# keychain_rev4.net
KiCad netlist of a schematic drawn in EAGLE
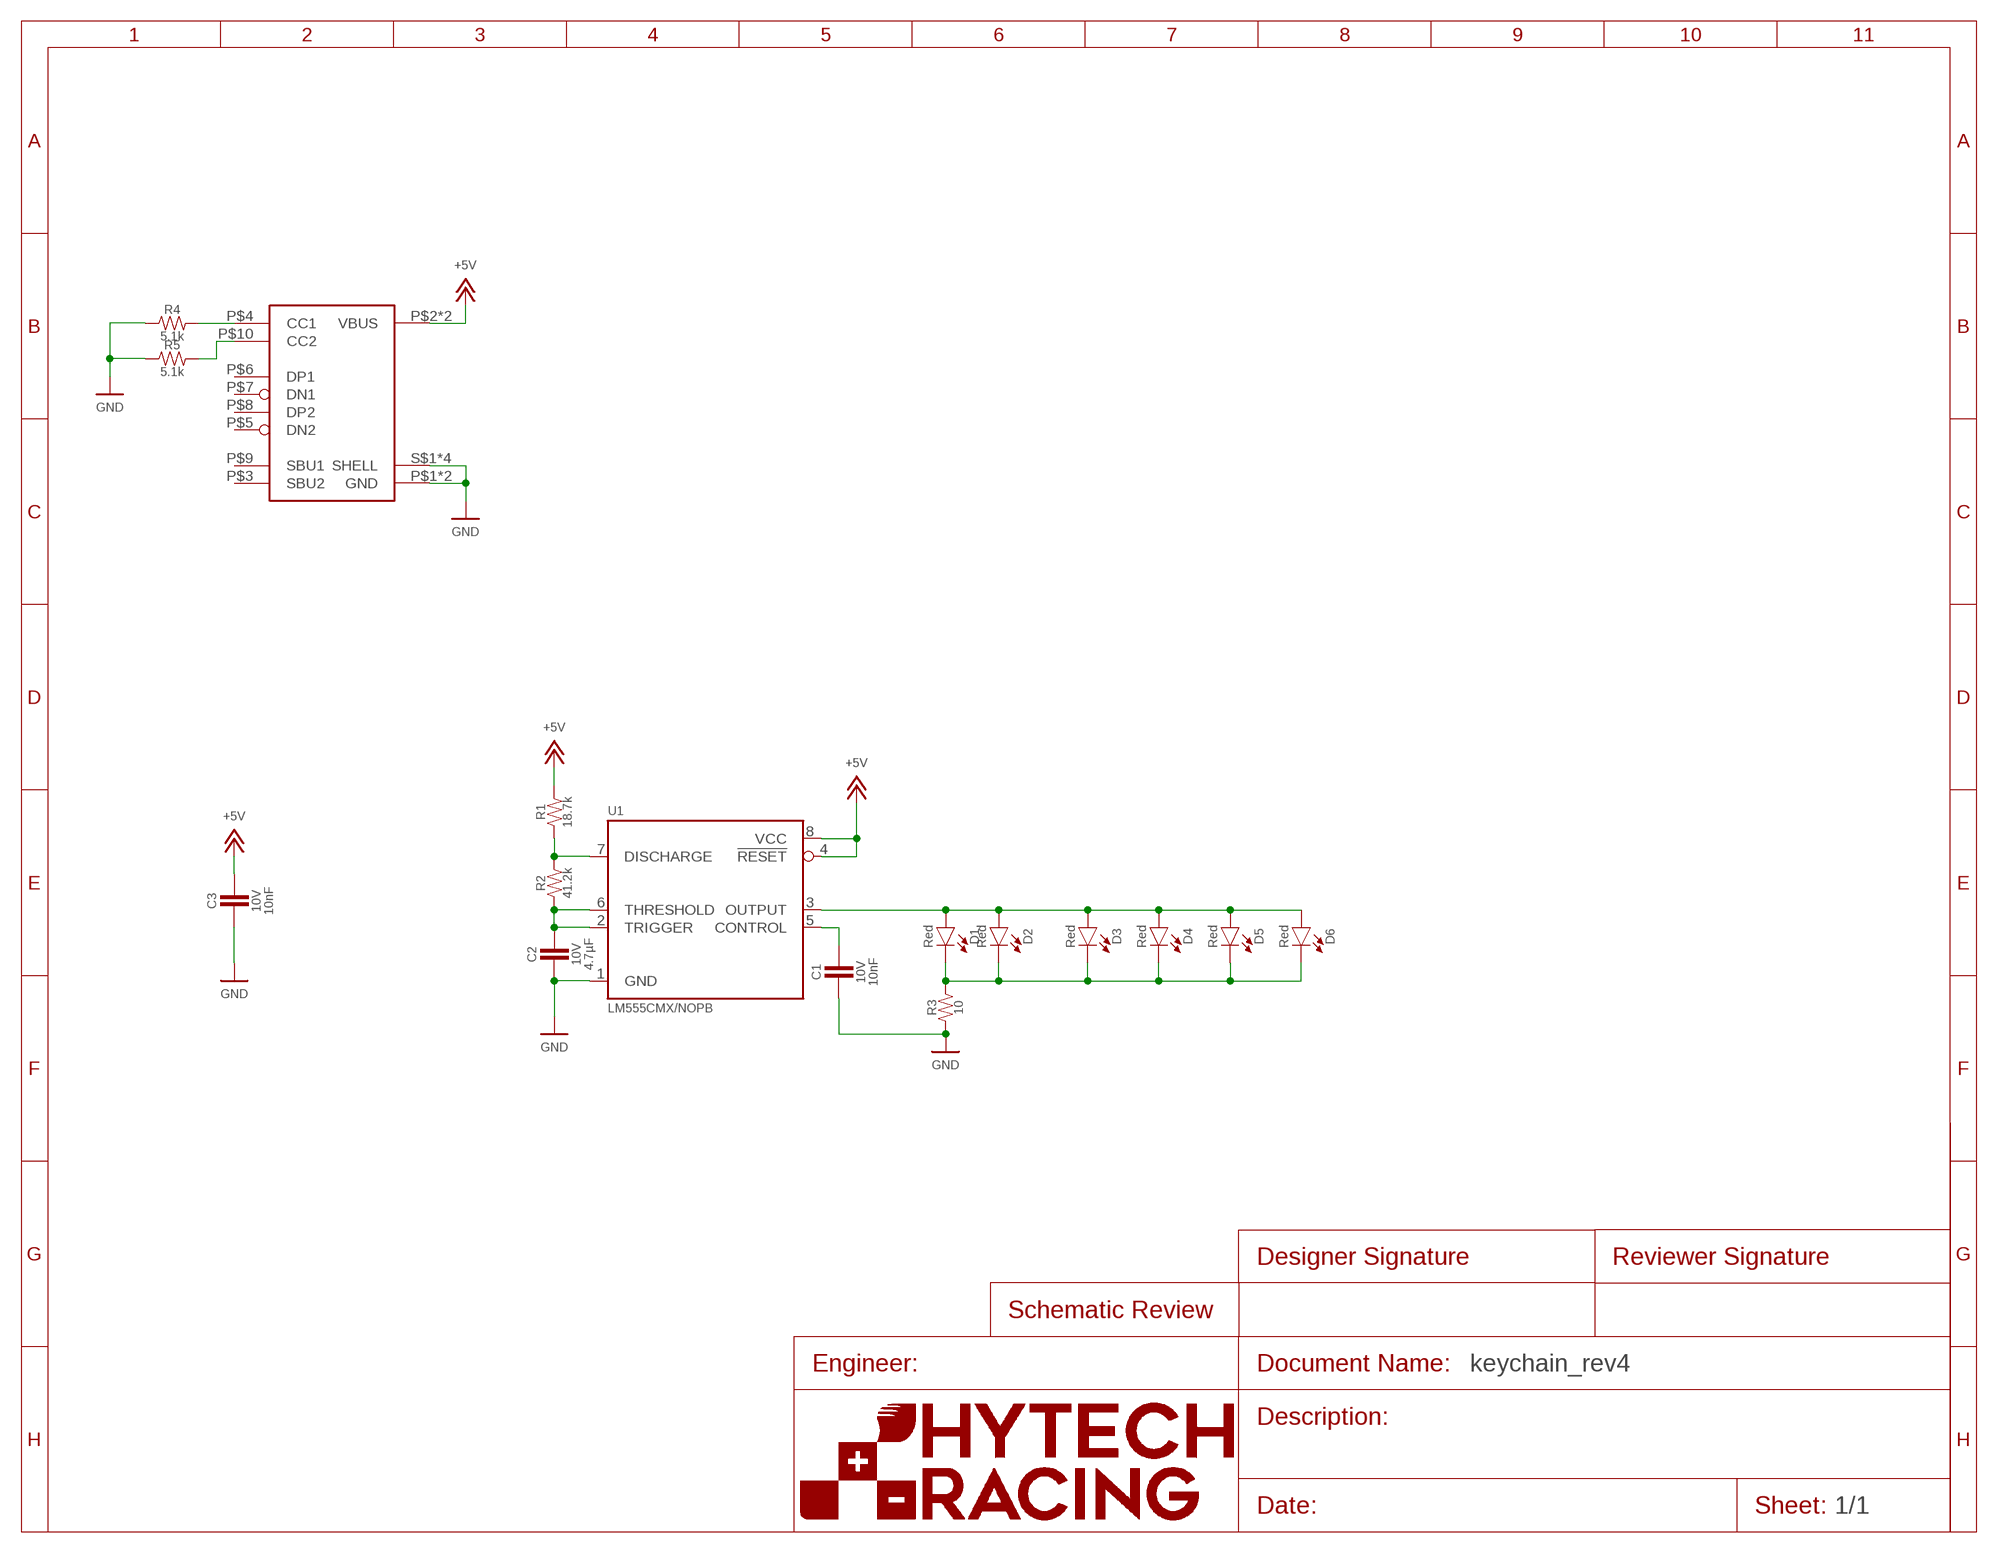
[diagram p0: schematic, sheet 1]

(export (version "E")
  (design (tool "Eeschema 10.0.6"))
  (components
    (comp (ref "C1")
      (value "CAPACITOR_0603_10V_10NF")
      (footprint "eagle-import:0603-CAP")
      (fields
        (field (name "CAPACITANCE") "10nF")
        (field (name "MANUFACTURER") "Yageo")
        (field (name "MPN") "CC0603KRX7R6BB103")
        (field (name "TOLERANCE") "10%")
        (field (name "VOLTAGE") "10V")
      )
      (libsource (lib "eagle-import") (part "CAPACITOR_?_060310V_10NF"))
    )
    (comp (ref "C2")
      (value "CAPACITOR_0603_10V_4.7UF")
      (footprint "eagle-import:0603-CAP")
      (fields
        (field (name "CAPACITANCE") "4.7µF")
        (field (name "MANUFACTURER") "Samsung Electro-Mechanics")
        (field (name "MPN") "CL10A475KP8NNNC")
        (field (name "TOLERANCE") "10%")
        (field (name "VOLTAGE") "10V")
      )
      (libsource (lib "eagle-import") (part "CAPACITOR_?_060310V_4.7UF"))
    )
    (comp (ref "C3")
      (value "CAPACITOR_0603_10V_10NF")
      (footprint "eagle-import:0603-CAP")
      (fields
        (field (name "CAPACITANCE") "10nF")
        (field (name "MANUFACTURER") "Yageo")
        (field (name "MPN") "CC0603KRX7R6BB103")
        (field (name "TOLERANCE") "10%")
        (field (name "VOLTAGE") "10V")
      )
      (libsource (lib "eagle-import") (part "CAPACITOR_?_060310V_10NF"))
    )
    (comp (ref "D1")
      (value "LED_0603_RED")
      (footprint "eagle-import:0603-LED")
      (fields
        (field (name "COLOR") "Red")
        (field (name "MANUFACTURER") "Kingbright")
        (field (name "MPN") "APT1608SECK/J3-PRV")
      )
      (libsource (lib "eagle-import") (part "LED_?_0603RED"))
    )
    (comp (ref "D2")
      (value "LED_0603_RED")
      (footprint "eagle-import:0603-LED")
      (fields
        (field (name "COLOR") "Red")
        (field (name "MANUFACTURER") "Kingbright")
        (field (name "MPN") "APT1608SECK/J3-PRV")
      )
      (libsource (lib "eagle-import") (part "LED_?_0603RED"))
    )
    (comp (ref "D3")
      (value "LED_0603_RED")
      (footprint "eagle-import:0603-LED")
      (fields
        (field (name "COLOR") "Red")
        (field (name "MANUFACTURER") "Kingbright")
        (field (name "MPN") "APT1608SECK/J3-PRV")
      )
      (libsource (lib "eagle-import") (part "LED_?_0603RED"))
    )
    (comp (ref "D4")
      (value "LED_0603_RED")
      (footprint "eagle-import:0603-LED")
      (fields
        (field (name "COLOR") "Red")
        (field (name "MANUFACTURER") "Kingbright")
        (field (name "MPN") "APT1608SECK/J3-PRV")
      )
      (libsource (lib "eagle-import") (part "LED_?_0603RED"))
    )
    (comp (ref "D5")
      (value "LED_0603_RED")
      (footprint "eagle-import:0603-LED")
      (fields
        (field (name "COLOR") "Red")
        (field (name "MANUFACTURER") "Kingbright")
        (field (name "MPN") "APT1608SECK/J3-PRV")
      )
      (libsource (lib "eagle-import") (part "LED_?_0603RED"))
    )
    (comp (ref "D6")
      (value "LED_0603_RED")
      (footprint "eagle-import:0603-LED")
      (fields
        (field (name "COLOR") "Red")
        (field (name "MANUFACTURER") "Kingbright")
        (field (name "MPN") "APT1608SECK/J3-PRV")
      )
      (libsource (lib "eagle-import") (part "LED_?_0603RED"))
    )
    (comp (ref "J1")
      (value "USB4110")
      (footprint "eagle-import:USB4110")
      (fields (field (name "MANUFACTURER") "GCT") (field (name "MPN") "USB4110 "))
      (libsource (lib "eagle-import") (part "USB4110"))
    )
    (comp (ref "R1")
      (value "RESISTOR_0603_18.7K")
      (footprint "eagle-import:0603-RES")
      (fields
        (field (name "MANUFACTURER") "Yageo")
        (field (name "MPN") "RC0603FR-0718K7L")
        (field (name "POWER") "0.1W")
        (field (name "RESISTANCE") "18.7k")
      )
      (libsource (lib "eagle-import") (part "RESISTOR_?_060318.7K"))
    )
    (comp (ref "R2")
      (value "RESISTOR_0603_41.2K")
      (footprint "eagle-import:0603-RES")
      (fields
        (field (name "MANUFACTURER") "Panasonic Electronic Components")
        (field (name "MPN") " ERJ-PB3B4122V")
        (field (name "POWER") "0.2W")
        (field (name "RESISTANCE") "41.2k")
      )
      (libsource (lib "eagle-import") (part "RESISTOR_?_060341.2K"))
    )
    (comp (ref "R3")
      (value "RESISTOR_0603_10")
      (footprint "eagle-import:0603-RES")
      (fields
        (field (name "MANUFACTURER") "Yageo")
        (field (name "MPN") "RC0603FR-0710RL")
        (field (name "POWER") "0.1W")
        (field (name "RESISTANCE") "10")
      )
      (libsource (lib "eagle-import") (part "RESISTOR_?_060310"))
    )
    (comp (ref "R4")
      (value "RESISTOR_0603_5.1K")
      (footprint "eagle-import:0603-RES")
      (fields
        (field (name "MANUFACTURER") "Yageo")
        (field (name "MPN") "RC0603FR-075K1L")
        (field (name "POWER") "0.1W")
        (field (name "RESISTANCE") "5.1k")
      )
      (libsource (lib "eagle-import") (part "RESISTOR_?_06035.1K"))
    )
    (comp (ref "R5")
      (value "RESISTOR_0603_5.1K")
      (footprint "eagle-import:0603-RES")
      (fields
        (field (name "MANUFACTURER") "Yageo")
        (field (name "MPN") "RC0603FR-075K1L")
        (field (name "POWER") "0.1W")
        (field (name "RESISTANCE") "5.1k")
      )
      (libsource (lib "eagle-import") (part "RESISTOR_?_06035.1K"))
    )
    (comp (ref "U1")
      (value "LM555")
      (footprint "eagle-import:SOIC-08(NARROW,0.15_)")
      (fields (field (name "MANUFACTURER") "Texas Instruments") (field (name "MPN") "LM555CMX/NOPB"))
      (libsource (lib "eagle-import") (part "555LM"))
    )
  )
  (nets
    (net (code "1") (name "+5V") (class "Default")
      (node (ref "C3") (pin "1") (pinfunction "1_1") (pintype "passive"))
      (node (ref "J1") (pin "P$11") (pinfunction "VBUS_P$11") (pintype "power_in"))
      (node (ref "J1") (pin "P$2") (pinfunction "VBUS_P$2") (pintype "power_in"))
      (node (ref "R1") (pin "2") (pinfunction "2_2") (pintype "passive"))
      (node (ref "U1") (pin "4") (pinfunction "~{RESET}_4") (pintype "input"))
      (node (ref "U1") (pin "8") (pinfunction "VCC_8") (pintype "power_in"))
    )
    (net (code "2") (name "GND") (class "Default")
      (node (ref "C1") (pin "2") (pinfunction "2_2") (pintype "passive"))
      (node (ref "C2") (pin "2") (pinfunction "2_2") (pintype "passive"))
      (node (ref "C3") (pin "2") (pinfunction "2_2") (pintype "passive"))
      (node (ref "J1") (pin "P$1") (pinfunction "GND_P$1") (pintype "power_in"))
      (node (ref "J1") (pin "P$12") (pinfunction "GND_P$12") (pintype "power_in"))
      (node (ref "J1") (pin "S$1") (pinfunction "SHELL_S$1") (pintype "power_in"))
      (node (ref "J1") (pin "S$2") (pinfunction "SHELL_S$2") (pintype "power_in"))
      (node (ref "J1") (pin "S$3") (pinfunction "SHELL_S$3") (pintype "power_in"))
      (node (ref "J1") (pin "S$4") (pinfunction "SHELL_S$4") (pintype "power_in"))
      (node (ref "R3") (pin "1") (pinfunction "1_1") (pintype "passive"))
      (node (ref "R4") (pin "1") (pinfunction "1_1") (pintype "passive"))
      (node (ref "R5") (pin "1") (pinfunction "1_1") (pintype "passive"))
      (node (ref "U1") (pin "1") (pinfunction "GND_1") (pintype "power_in"))
    )
    (net (code "3") (name "Net-(D1-A)") (class "Default")
      (node (ref "D1") (pin "2") (pinfunction "A_2") (pintype "passive"))
      (node (ref "D2") (pin "2") (pinfunction "A_2") (pintype "passive"))
      (node (ref "D3") (pin "2") (pinfunction "A_2") (pintype "passive"))
      (node (ref "D4") (pin "2") (pinfunction "A_2") (pintype "passive"))
      (node (ref "D5") (pin "2") (pinfunction "A_2") (pintype "passive"))
      (node (ref "D6") (pin "2") (pinfunction "A_2") (pintype "passive"))
      (node (ref "U1") (pin "3") (pinfunction "OUTPUT_3") (pintype "output"))
    )
    (net (code "4") (name "Net-(D1-C)") (class "Default")
      (node (ref "D1") (pin "1") (pinfunction "C_1") (pintype "passive"))
      (node (ref "D2") (pin "1") (pinfunction "C_1") (pintype "passive"))
      (node (ref "D3") (pin "1") (pinfunction "C_1") (pintype "passive"))
      (node (ref "D4") (pin "1") (pinfunction "C_1") (pintype "passive"))
      (node (ref "D5") (pin "1") (pinfunction "C_1") (pintype "passive"))
      (node (ref "D6") (pin "1") (pinfunction "C_1") (pintype "passive"))
      (node (ref "R3") (pin "2") (pinfunction "2_2") (pintype "passive"))
    )
    (net (code "5") (name "Net-(J1-CC1)") (class "Default")
      (node (ref "J1") (pin "P$4") (pinfunction "CC1_P$4") (pintype "passive"))
      (node (ref "R4") (pin "2") (pinfunction "2_2") (pintype "passive"))
    )
    (net (code "6") (name "Net-(J1-CC2)") (class "Default")
      (node (ref "J1") (pin "P$10") (pinfunction "CC2_P$10") (pintype "passive"))
      (node (ref "R5") (pin "2") (pinfunction "2_2") (pintype "passive"))
    )
    (net (code "7") (name "Net-(U1-CONTROL)") (class "Default")
      (node (ref "C1") (pin "1") (pinfunction "1_1") (pintype "passive"))
      (node (ref "U1") (pin "5") (pinfunction "CONTROL_5") (pintype "input"))
    )
    (net (code "8") (name "Net-(U1-DISCHARGE)") (class "Default")
      (node (ref "R1") (pin "1") (pinfunction "1_1") (pintype "passive"))
      (node (ref "R2") (pin "2") (pinfunction "2_2") (pintype "passive"))
      (node (ref "U1") (pin "7") (pinfunction "DISCHARGE_7") (pintype "input"))
    )
    (net (code "9") (name "Net-(U1-THRESHOLD)") (class "Default")
      (node (ref "C2") (pin "1") (pinfunction "1_1") (pintype "passive"))
      (node (ref "R2") (pin "1") (pinfunction "1_1") (pintype "passive"))
      (node (ref "U1") (pin "2") (pinfunction "TRIGGER_2") (pintype "input"))
      (node (ref "U1") (pin "6") (pinfunction "THRESHOLD_6") (pintype "input"))
    )
    (net (code "10") (name "unconnected-(J1-DN1-PadP$7)") (class "Default")
      (node (ref "J1") (pin "P$7") (pinfunction "DN1_P$7") (pintype "bidirectional"))
    )
    (net (code "11") (name "unconnected-(J1-DN2-PadP$5)") (class "Default")
      (node (ref "J1") (pin "P$5") (pinfunction "DN2_P$5") (pintype "bidirectional"))
    )
    (net (code "12") (name "unconnected-(J1-DP1-PadP$6)") (class "Default")
      (node (ref "J1") (pin "P$6") (pinfunction "DP1_P$6") (pintype "bidirectional"))
    )
    (net (code "13") (name "unconnected-(J1-DP2-PadP$8)") (class "Default")
      (node (ref "J1") (pin "P$8") (pinfunction "DP2_P$8") (pintype "bidirectional"))
    )
    (net (code "14") (name "unconnected-(J1-SBU1-PadP$9)") (class "Default")
      (node (ref "J1") (pin "P$9") (pinfunction "SBU1_P$9") (pintype "bidirectional"))
    )
    (net (code "15") (name "unconnected-(J1-SBU2-PadP$3)") (class "Default")
      (node (ref "J1") (pin "P$3") (pinfunction "SBU2_P$3") (pintype "bidirectional"))
    )
  )
)
